# design.net
KiCad netlist of a schematic drawn in Altium Designer
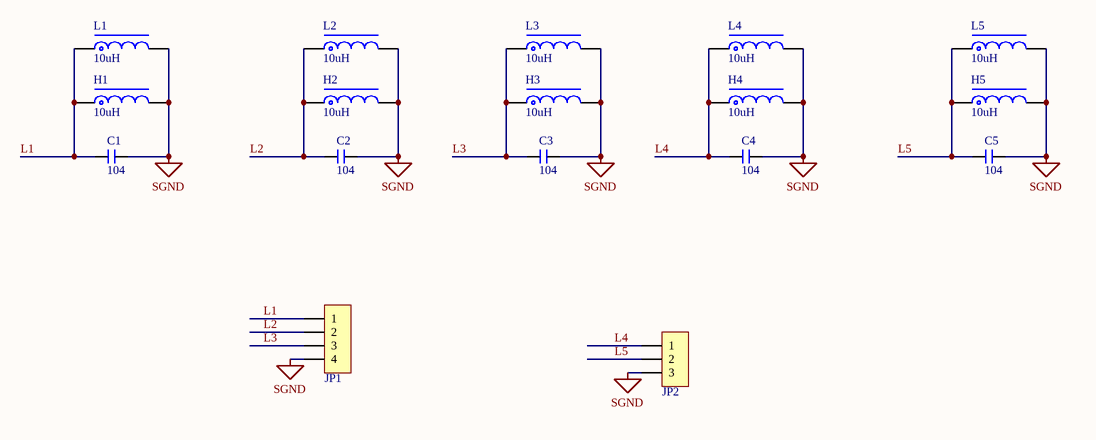
[diagram p0: 前瞻.SchDoc]

(export (version "E")
  (design (tool "Eeschema 10.0.6"))
  (components
    (comp (ref "C1")
      (value "104")
      (footprint "谐振电容")
      (description "贴片电容")
      (libsource (lib "0.1 - 电阻-电容-电感") (part "C"))
    )
    (comp (ref "C2")
      (value "104")
      (footprint "谐振电容")
      (description "贴片电容")
      (libsource (lib "0.1 - 电阻-电容-电感") (part "C"))
    )
    (comp (ref "C3")
      (value "104")
      (footprint "谐振电容")
      (description "贴片电容")
      (libsource (lib "0.1 - 电阻-电容-电感") (part "C"))
    )
    (comp (ref "C4")
      (value "104")
      (footprint "谐振电容")
      (description "贴片电容")
      (libsource (lib "0.1 - 电阻-电容-电感") (part "C"))
    )
    (comp (ref "C5")
      (value "104")
      (footprint "谐振电容")
      (description "贴片电容")
      (libsource (lib "0.1 - 电阻-电容-电感") (part "C"))
    )
    (comp (ref "H1")
      (value "10uH")
      (footprint "8*10工字电感")
      (description "工字电感")
      (libsource (lib "0.1 - 电阻-电容-电感") (part "L-PK"))
    )
    (comp (ref "H2")
      (value "10uH")
      (footprint "8*10工字电感")
      (description "工字电感")
      (libsource (lib "0.1 - 电阻-电容-电感") (part "L-PK"))
    )
    (comp (ref "H3")
      (value "10uH")
      (footprint "8*10工字电感")
      (description "工字电感")
      (libsource (lib "0.1 - 电阻-电容-电感") (part "L-PK"))
    )
    (comp (ref "H4")
      (value "10uH")
      (footprint "8*10工字电感")
      (description "工字电感")
      (libsource (lib "0.1 - 电阻-电容-电感") (part "L-PK"))
    )
    (comp (ref "H5")
      (value "10uH")
      (footprint "8*10工字电感")
      (description "工字电感")
      (libsource (lib "0.1 - 电阻-电容-电感") (part "L-PK"))
    )
    (comp (ref "JP1")
      (value "HDR-1X4")
      (footprint "HDR2.54-WI-4P")
      (description "4P接插件")
      (libsource (lib "5.4 - 接插件-脚距2.54 (100mil) ") (part "Header 4"))
    )
    (comp (ref "JP2")
      (value "HDR-1X3")
      (footprint "HDR2.54-WI-3P")
      (description "3P接插件")
      (libsource (lib "5.4 - 接插件-脚距2.54 (100mil) ") (part "Header 3"))
    )
    (comp (ref "L1")
      (value "10uH")
      (footprint "8*10工字电感")
      (description "工字电感")
      (libsource (lib "0.1 - 电阻-电容-电感") (part "L-PK"))
    )
    (comp (ref "L2")
      (value "10uH")
      (footprint "8*10工字电感")
      (description "工字电感")
      (libsource (lib "0.1 - 电阻-电容-电感") (part "L-PK"))
    )
    (comp (ref "L3")
      (value "10uH")
      (footprint "8*10工字电感")
      (description "工字电感")
      (libsource (lib "0.1 - 电阻-电容-电感") (part "L-PK"))
    )
    (comp (ref "L4")
      (value "10uH")
      (footprint "8*10工字电感")
      (description "工字电感")
      (libsource (lib "0.1 - 电阻-电容-电感") (part "L-PK"))
    )
    (comp (ref "L5")
      (value "10uH")
      (footprint "8*10工字电感")
      (description "工字电感")
      (libsource (lib "0.1 - 电阻-电容-电感") (part "L-PK"))
    )
  )
  (nets
    (net (code "1") (name "/L1") (class "Default")
      (node (ref "C1") (pin "1") (pinfunction "1_1") (pintype "passive"))
      (node (ref "H1") (pin "1") (pinfunction "1_1") (pintype "passive"))
      (node (ref "JP1") (pin "1") (pinfunction "1_1") (pintype "passive"))
      (node (ref "L1") (pin "1") (pinfunction "1_1") (pintype "passive"))
    )
    (net (code "2") (name "/L2") (class "Default")
      (node (ref "C2") (pin "1") (pinfunction "1_1") (pintype "passive"))
      (node (ref "H2") (pin "1") (pinfunction "1_1") (pintype "passive"))
      (node (ref "JP1") (pin "2") (pinfunction "2_2") (pintype "passive"))
      (node (ref "L2") (pin "1") (pinfunction "1_1") (pintype "passive"))
    )
    (net (code "3") (name "/L3") (class "Default")
      (node (ref "C3") (pin "1") (pinfunction "1_1") (pintype "passive"))
      (node (ref "H3") (pin "1") (pinfunction "1_1") (pintype "passive"))
      (node (ref "JP1") (pin "3") (pinfunction "3_3") (pintype "passive"))
      (node (ref "L3") (pin "1") (pinfunction "1_1") (pintype "passive"))
    )
    (net (code "4") (name "/L4") (class "Default")
      (node (ref "C4") (pin "1") (pinfunction "1_1") (pintype "passive"))
      (node (ref "H4") (pin "1") (pinfunction "1_1") (pintype "passive"))
      (node (ref "JP2") (pin "1") (pinfunction "1_1") (pintype "passive"))
      (node (ref "L4") (pin "1") (pinfunction "1_1") (pintype "passive"))
    )
    (net (code "5") (name "/L5") (class "Default")
      (node (ref "C5") (pin "1") (pinfunction "1_1") (pintype "passive"))
      (node (ref "H5") (pin "1") (pinfunction "1_1") (pintype "passive"))
      (node (ref "JP2") (pin "2") (pinfunction "2_2") (pintype "passive"))
      (node (ref "L5") (pin "1") (pinfunction "1_1") (pintype "passive"))
    )
    (net (code "6") (name "SGND") (class "Default")
      (node (ref "C1") (pin "2") (pinfunction "2_2") (pintype "passive"))
      (node (ref "C2") (pin "2") (pinfunction "2_2") (pintype "passive"))
      (node (ref "C3") (pin "2") (pinfunction "2_2") (pintype "passive"))
      (node (ref "C4") (pin "2") (pinfunction "2_2") (pintype "passive"))
      (node (ref "C5") (pin "2") (pinfunction "2_2") (pintype "passive"))
      (node (ref "H1") (pin "2") (pinfunction "2_2") (pintype "passive"))
      (node (ref "H2") (pin "2") (pinfunction "2_2") (pintype "passive"))
      (node (ref "H3") (pin "2") (pinfunction "2_2") (pintype "passive"))
      (node (ref "H4") (pin "2") (pinfunction "2_2") (pintype "passive"))
      (node (ref "H5") (pin "2") (pinfunction "2_2") (pintype "passive"))
      (node (ref "JP1") (pin "4") (pinfunction "4_4") (pintype "passive"))
      (node (ref "JP2") (pin "3") (pinfunction "3_3") (pintype "passive"))
      (node (ref "L1") (pin "2") (pinfunction "2_2") (pintype "passive"))
      (node (ref "L2") (pin "2") (pinfunction "2_2") (pintype "passive"))
      (node (ref "L3") (pin "2") (pinfunction "2_2") (pintype "passive"))
      (node (ref "L4") (pin "2") (pinfunction "2_2") (pintype "passive"))
      (node (ref "L5") (pin "2") (pinfunction "2_2") (pintype "passive"))
    )
  )
)
